# Com_PC.net
KiCad netlist of a schematic drawn in Altium Designer
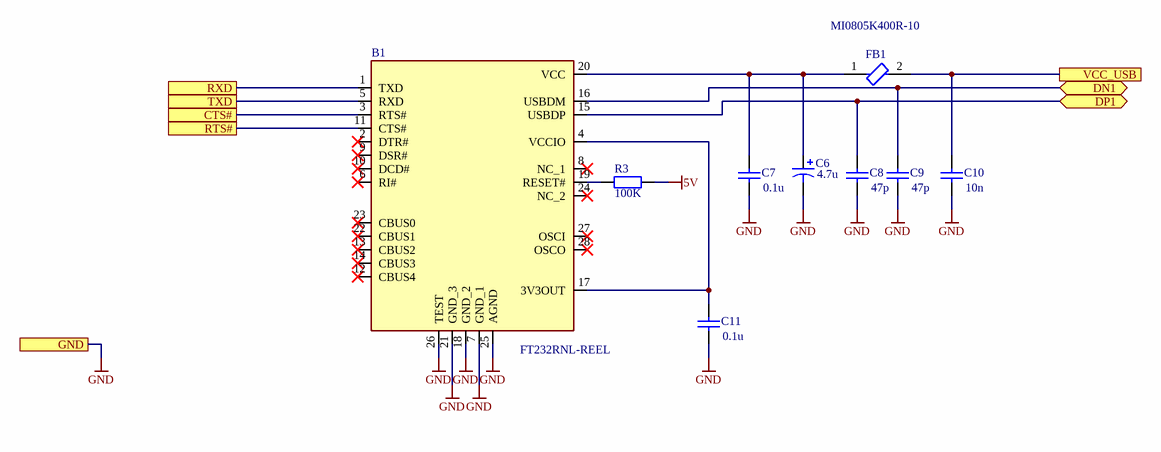
[diagram p0: Com_PC.SchDoc]

(export (version "E")
  (design (tool "Eeschema 10.0.6"))
  (components
    (comp (ref "B1")
      (value "FT232RNL-REEL")
      (footprint "SOP65P780X200-28N")
      (description "UART Interface IC USB Full Speed to Serial UART IC, Includes Oscillator and EEPROM, SSOP-28")
      (fields (field (name "MOUSER PART NUMBER") "895-FT232RNL-REEL"))
      (libsource (lib "2225B_VumetreFrequenciel") (part "FT232RNL-REEL"))
    )
    (comp (ref "C6")
      (value "4.7u")
      (footprint "PCAP_SVP_A5_PAN-M")
      (description "Polarized Capacitor (Radial)")
      (fields (field (name "PUBLISHER") "Altium Limited"))
      (libsource (lib "Miscellaneous Devices") (part "Cap Pol1"))
    )
    (comp (ref "C7")
      (value "0.1u")
      (footprint "C0805")
      (description "Capacitor")
      (fields (field (name "PUBLISHER") "Altium Limited"))
      (libsource (lib "Miscellaneous Devices") (part "Cap"))
    )
    (comp (ref "C8")
      (value "47p")
      (footprint "C0805")
      (description "Capacitor")
      (fields (field (name "PUBLISHER") "Altium Limited"))
      (libsource (lib "Miscellaneous Devices") (part "Cap"))
    )
    (comp (ref "C9")
      (value "47p")
      (footprint "C0805")
      (description "Capacitor")
      (fields (field (name "PUBLISHER") "Altium Limited"))
      (libsource (lib "Miscellaneous Devices") (part "Cap"))
    )
    (comp (ref "C10")
      (value "10n")
      (footprint "C0805")
      (description "Capacitor")
      (fields (field (name "PUBLISHER") "Altium Limited"))
      (libsource (lib "Miscellaneous Devices") (part "Cap"))
    )
    (comp (ref "C11")
      (value "0.1u")
      (footprint "C0805")
      (description "Capacitor")
      (fields (field (name "PUBLISHER") "Altium Limited"))
      (libsource (lib "Miscellaneous Devices") (part "Cap"))
    )
    (comp (ref "FB1")
      (value "MI0805K400R-10")
      (footprint "FP-MI0805-MFG")
      (description "FERRITE BEAD 40 OHM 0805 1LN")
      (fields (field (name "TOLERANCE") "25%"))
      (libsource (lib "Altium Content Vault") (part "5f30dd21d616792df468990f7003faa"))
    )
    (comp (ref "R3")
      (value "100K")
      (footprint "RESC2012X06M")
      (description "Resistor")
      (fields (field (name "PUBLISHER") "Altium Limited"))
      (libsource (lib "Miscellaneous Devices") (part "Res2"))
    )
  )
  (nets
    (net (code "1") (name "/CTS#") (class "Default")
      (node (ref "B1") (pin "3") (pinfunction "RTS#_3") (pintype "passive"))
    )
    (net (code "2") (name "/DN1") (class "Default")
      (node (ref "B1") (pin "16") (pinfunction "USBDM_16") (pintype "passive"))
      (node (ref "C9") (pin "1") (pinfunction "1_1") (pintype "passive"))
    )
    (net (code "3") (name "/DP1") (class "Default")
      (node (ref "B1") (pin "15") (pinfunction "USBDP_15") (pintype "passive"))
      (node (ref "C8") (pin "1") (pinfunction "1_1") (pintype "passive"))
    )
    (net (code "4") (name "/RTS#") (class "Default")
      (node (ref "B1") (pin "11") (pinfunction "CTS#_11") (pintype "passive"))
    )
    (net (code "5") (name "/RXD") (class "Default")
      (node (ref "B1") (pin "1") (pinfunction "TXD_1") (pintype "passive"))
    )
    (net (code "6") (name "/TXD") (class "Default")
      (node (ref "B1") (pin "5") (pinfunction "RXD_5") (pintype "passive"))
    )
    (net (code "7") (name "/VCC_USB") (class "Default")
      (node (ref "C10") (pin "1") (pinfunction "1_1") (pintype "passive"))
      (node (ref "FB1") (pin "2") (pinfunction "2_2") (pintype "passive"))
    )
    (net (code "8") (name "5V") (class "Default")
      (node (ref "R3") (pin "1") (pinfunction "1_1") (pintype "passive"))
    )
    (net (code "9") (name "GND") (class "Default")
      (node (ref "B1") (pin "18") (pinfunction "GND_2_18") (pintype "passive"))
      (node (ref "B1") (pin "21") (pinfunction "GND_3_21") (pintype "passive"))
      (node (ref "B1") (pin "25") (pinfunction "AGND_25") (pintype "passive"))
      (node (ref "B1") (pin "26") (pinfunction "TEST_26") (pintype "passive"))
      (node (ref "B1") (pin "7") (pinfunction "GND_1_7") (pintype "passive"))
      (node (ref "C10") (pin "2") (pinfunction "2_2") (pintype "passive"))
      (node (ref "C11") (pin "2") (pinfunction "2_2") (pintype "passive"))
      (node (ref "C6") (pin "2") (pinfunction "2_2") (pintype "passive"))
      (node (ref "C7") (pin "2") (pinfunction "2_2") (pintype "passive"))
      (node (ref "C8") (pin "2") (pinfunction "2_2") (pintype "passive"))
      (node (ref "C9") (pin "2") (pinfunction "2_2") (pintype "passive"))
    )
    (net (code "10") (name "Net-(B1-3V3OUT)") (class "Default")
      (node (ref "B1") (pin "17") (pinfunction "3V3OUT_17") (pintype "passive"))
      (node (ref "B1") (pin "4") (pinfunction "VCCIO_4") (pintype "passive"))
      (node (ref "C11") (pin "1") (pinfunction "1_1") (pintype "passive"))
    )
    (net (code "11") (name "Net-(B1-RESET#)") (class "Default")
      (node (ref "B1") (pin "19") (pinfunction "RESET#_19") (pintype "passive"))
      (node (ref "R3") (pin "2") (pinfunction "2_2") (pintype "passive"))
    )
    (net (code "12") (name "Net-(B1-VCC)") (class "Default")
      (node (ref "B1") (pin "20") (pinfunction "VCC_20") (pintype "passive"))
      (node (ref "C6") (pin "1") (pinfunction "1_1") (pintype "passive"))
      (node (ref "C7") (pin "1") (pinfunction "1_1") (pintype "passive"))
      (node (ref "FB1") (pin "1") (pinfunction "1_1") (pintype "passive"))
    )
    (net (code "13") (name "unconnected-(B1-CBUS0-Pad23)") (class "Default")
      (node (ref "B1") (pin "23") (pinfunction "CBUS0_23") (pintype "passive+no_connect"))
    )
    (net (code "14") (name "unconnected-(B1-CBUS1-Pad22)") (class "Default")
      (node (ref "B1") (pin "22") (pinfunction "CBUS1_22") (pintype "passive+no_connect"))
    )
    (net (code "15") (name "unconnected-(B1-CBUS2-Pad13)") (class "Default")
      (node (ref "B1") (pin "13") (pinfunction "CBUS2_13") (pintype "passive+no_connect"))
    )
    (net (code "16") (name "unconnected-(B1-CBUS3-Pad14)") (class "Default")
      (node (ref "B1") (pin "14") (pinfunction "CBUS3_14") (pintype "passive+no_connect"))
    )
    (net (code "17") (name "unconnected-(B1-CBUS4-Pad12)") (class "Default")
      (node (ref "B1") (pin "12") (pinfunction "CBUS4_12") (pintype "passive+no_connect"))
    )
    (net (code "18") (name "unconnected-(B1-DCD#-Pad10)") (class "Default")
      (node (ref "B1") (pin "10") (pinfunction "DCD#_10") (pintype "passive+no_connect"))
    )
    (net (code "19") (name "unconnected-(B1-DSR#-Pad9)") (class "Default")
      (node (ref "B1") (pin "9") (pinfunction "DSR#_9") (pintype "passive+no_connect"))
    )
    (net (code "20") (name "unconnected-(B1-DTR#-Pad2)") (class "Default")
      (node (ref "B1") (pin "2") (pinfunction "DTR#_2") (pintype "passive+no_connect"))
    )
    (net (code "21") (name "unconnected-(B1-NC_1-Pad8)") (class "Default")
      (node (ref "B1") (pin "8") (pinfunction "NC_1_8") (pintype "passive+no_connect"))
    )
    (net (code "22") (name "unconnected-(B1-NC_2-Pad24)") (class "Default")
      (node (ref "B1") (pin "24") (pinfunction "NC_2_24") (pintype "passive+no_connect"))
    )
    (net (code "23") (name "unconnected-(B1-OSCI-Pad27)") (class "Default")
      (node (ref "B1") (pin "27") (pinfunction "OSCI_27") (pintype "passive+no_connect"))
    )
    (net (code "24") (name "unconnected-(B1-OSCO-Pad28)") (class "Default")
      (node (ref "B1") (pin "28") (pinfunction "OSCO_28") (pintype "passive+no_connect"))
    )
    (net (code "25") (name "unconnected-(B1-RI#-Pad6)") (class "Default")
      (node (ref "B1") (pin "6") (pinfunction "RI#_6") (pintype "passive+no_connect"))
    )
  )
)
